# GDEnvSensorNode_1_4f.net
KiCad netlist of a schematic drawn in EAGLE
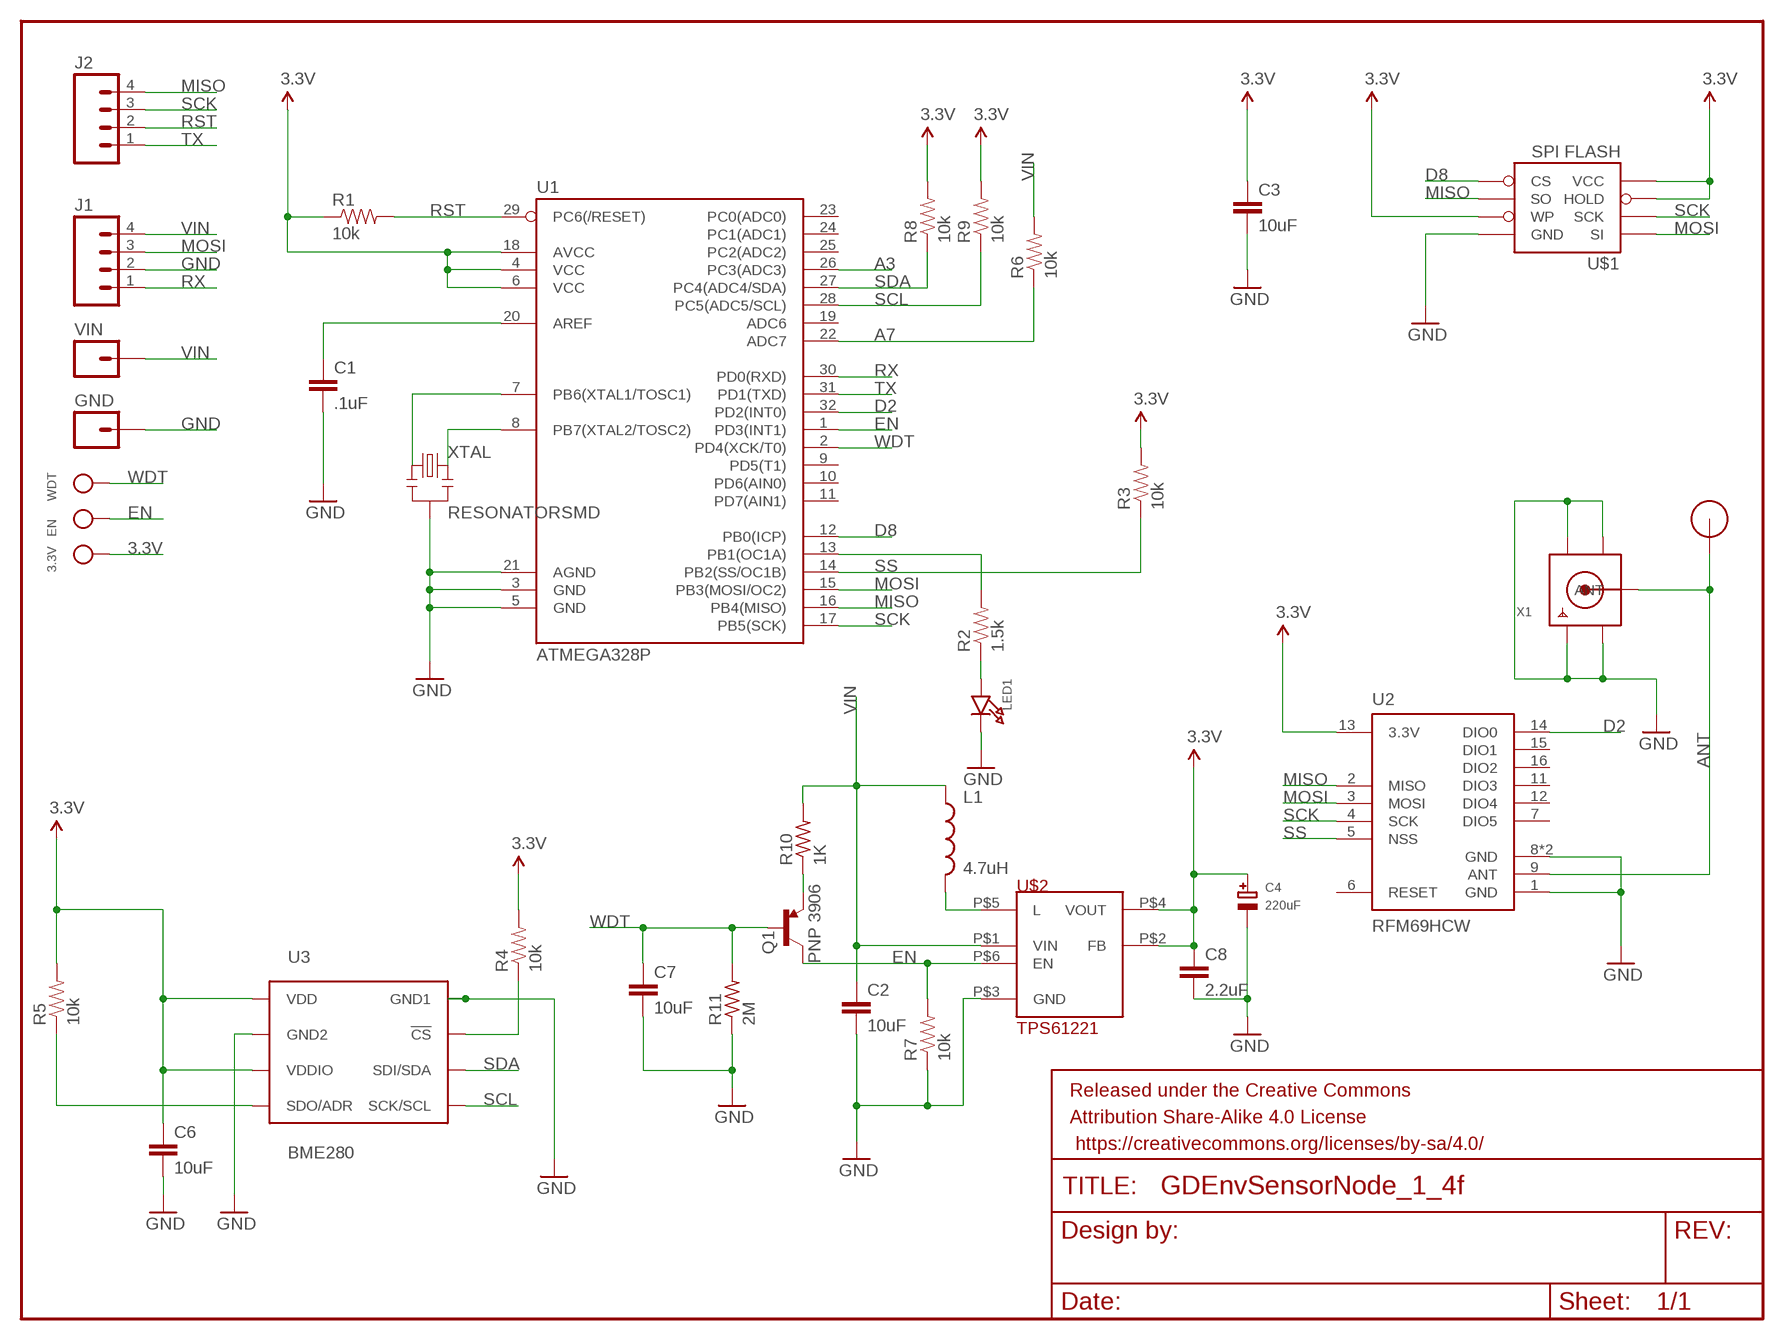
[diagram p0: schematic, sheet 1]

(export (version "E")
  (design (tool "Eeschema 10.0.6"))
  (components
    (comp (ref "3.3V")
      (value "TESTPOINTROUND1MM")
      (footprint "eagle-import:TESTPOINT_ROUND_1MM")
      (libsource (lib "eagle-import") (part "TESTPOINTROUND1MM"))
    )
    (comp (ref "C1")
      (value ".1uF")
      (footprint "eagle-import:0805")
      (libsource (lib "eagle-import") (part "CAP0805"))
    )
    (comp (ref "C2")
      (value "10uF")
      (footprint "eagle-import:0805")
      (libsource (lib "eagle-import") (part "CAP0805"))
    )
    (comp (ref "C3")
      (value "10uF")
      (footprint "eagle-import:0805")
      (libsource (lib "eagle-import") (part "CAP0805"))
    )
    (comp (ref "C4")
      (value "220uF")
      (footprint "eagle-import:EIA7343-31_D-R")
      (libsource (lib "eagle-import") (part "CAP_TANTALUMD/7343_REFLOW"))
    )
    (comp (ref "C6")
      (value "10uF")
      (footprint "eagle-import:0805")
      (libsource (lib "eagle-import") (part "CAP0805"))
    )
    (comp (ref "C7")
      (value "10uF")
      (footprint "eagle-import:0805")
      (libsource (lib "eagle-import") (part "CAP0805"))
    )
    (comp (ref "C8")
      (value "2.2uF")
      (footprint "eagle-import:0805")
      (libsource (lib "eagle-import") (part "CAP0805"))
    )
    (comp (ref "EN")
      (value "TESTPOINTROUND1MM")
      (footprint "eagle-import:TESTPOINT_ROUND_1MM")
      (libsource (lib "eagle-import") (part "TESTPOINTROUND1MM"))
    )
    (comp (ref "FRAME1")
      (value "FRAME-LETTER")
      (footprint "eagle-import:CREATIVE_COMMONS")
      (libsource (lib "eagle-import") (part "FRAME-LETTER"))
    )
    (comp (ref "GND")
      (value "M01PTH_2MM")
      (footprint "eagle-import:1X01_2MM")
      (libsource (lib "eagle-import") (part "M01PTH_2MM"))
    )
    (comp (ref "J1")
      (value "M04PTH")
      (footprint "eagle-import:1X04")
      (libsource (lib "eagle-import") (part "M04PTH"))
    )
    (comp (ref "J2")
      (value "M04PTH")
      (footprint "eagle-import:1X04")
      (libsource (lib "eagle-import") (part "M04PTH"))
    )
    (comp (ref "L1")
      (value "4.7uH")
      (footprint "eagle-import:1210")
      (libsource (lib "eagle-import") (part "INDUCTOR1210"))
    )
    (comp (ref "LED1")
      (value "LED0805")
      (footprint "eagle-import:CHIPLED_0805")
      (libsource (lib "eagle-import") (part "LED0805"))
    )
    (comp (ref "Q1")
      (value "PNP 3906")
      (footprint "eagle-import:SOT23-3")
      (libsource (lib "eagle-import") (part "TRANSISTOR_PNPPMBT3906"))
    )
    (comp (ref "R1")
      (value "10k")
      (footprint "eagle-import:0805")
      (libsource (lib "eagle-import") (part "RESISTOR0805-RES"))
    )
    (comp (ref "R2")
      (value "1.5k")
      (footprint "eagle-import:0805")
      (libsource (lib "eagle-import") (part "RESISTOR0805-RES"))
    )
    (comp (ref "R3")
      (value "10k")
      (footprint "eagle-import:0805")
      (libsource (lib "eagle-import") (part "RESISTOR0805-RES"))
    )
    (comp (ref "R4")
      (value "10k")
      (footprint "eagle-import:0805")
      (libsource (lib "eagle-import") (part "RESISTOR0805-RES"))
    )
    (comp (ref "R5")
      (value "10k")
      (footprint "eagle-import:0805")
      (libsource (lib "eagle-import") (part "RESISTOR0805-RES"))
    )
    (comp (ref "R6")
      (value "10k")
      (footprint "eagle-import:0805")
      (libsource (lib "eagle-import") (part "RESISTOR0805-RES"))
    )
    (comp (ref "R7")
      (value "10k")
      (footprint "eagle-import:0805")
      (libsource (lib "eagle-import") (part "RESISTOR0805-RES"))
    )
    (comp (ref "R8")
      (value "10k")
      (footprint "eagle-import:0805")
      (libsource (lib "eagle-import") (part "RESISTOR0805-RES"))
    )
    (comp (ref "R9")
      (value "10k")
      (footprint "eagle-import:0805")
      (libsource (lib "eagle-import") (part "RESISTOR0805-RES"))
    )
    (comp (ref "R10")
      (value "1K")
      (footprint "eagle-import:R0805")
      (libsource (lib "eagle-import") (part "R-US_R0805"))
    )
    (comp (ref "R11")
      (value "2M")
      (footprint "eagle-import:R0805")
      (libsource (lib "eagle-import") (part "R-US_R0805"))
    )
    (comp (ref "U$1")
      (value "SPI FLASH")
      (footprint "eagle-import:SO08")
      (libsource (lib "eagle-import") (part "AT25F512BJEDEC_3.9MM"))
    )
    (comp (ref "U$2")
      (value "TPS61221")
      (footprint "eagle-import:TPS61221")
      (fields (field (name "MF") "Texas Instruments"))
      (libsource (lib "eagle-import") (part "TPS61221"))
    )
    (comp (ref "U$4")
      (value "RFM12B_ANTENNA")
      (footprint "eagle-import:RFM12B-ANTENNA")
      (libsource (lib "eagle-import") (part "RFM12B_ANTENNA"))
    )
    (comp (ref "U1")
      (value "ATMEGA328P")
      (footprint "eagle-import:TQFP32-08")
      (libsource (lib "eagle-import") (part "ATMEGA328P_TQFP"))
    )
    (comp (ref "U2")
      (value "RFM69HCW")
      (footprint "eagle-import:RFM69HCW-XXXS2")
      (libsource (lib "eagle-import") (part "RFM69HCW"))
    )
    (comp (ref "U3")
      (value "BME280")
      (footprint "eagle-import:BME280_LGA")
      (libsource (lib "eagle-import") (part "BME280"))
    )
    (comp (ref "VIN")
      (value "M01PTH_2MM")
      (footprint "eagle-import:1X01_2MM")
      (libsource (lib "eagle-import") (part "M01PTH_2MM"))
    )
    (comp (ref "WDT")
      (value "TESTPOINTROUND1MM")
      (footprint "eagle-import:TESTPOINT_ROUND_1MM")
      (libsource (lib "eagle-import") (part "TESTPOINTROUND1MM"))
    )
    (comp (ref "X1")
      (value "SMACONNECTOR_EDGE_UFL")
      (footprint "eagle-import:SMA_EDGELAUNCH_UFL")
      (libsource (lib "eagle-import") (part "SMACONNECTOR_EDGE_UFL"))
    )
    (comp (ref "XTAL")
      (value "RESONATORSMD")
      (footprint "eagle-import:RESONATOR-SMD")
      (libsource (lib "eagle-import") (part "RESONATORSMD"))
    )
  )
  (nets
    (net (code "1") (name "/A3") (class "Default")
      (node (ref "U1") (pin "26") (pinfunction "PC3(ADC3)_26") (pintype "bidirectional"))
    )
    (net (code "2") (name "/A7") (class "Default")
      (node (ref "R6") (pin "1") (pinfunction "1_1") (pintype "passive"))
      (node (ref "U1") (pin "22") (pinfunction "ADC7_22") (pintype "bidirectional"))
    )
    (net (code "3") (name "/ANT") (class "Default")
      (node (ref "U$4") (pin "P$1") (pinfunction "1_P$1") (pintype "bidirectional"))
      (node (ref "U2") (pin "9") (pinfunction "ANT_9") (pintype "passive"))
      (node (ref "X1") (pin "P") (pinfunction "ANT_P") (pintype "bidirectional"))
    )
    (net (code "4") (name "/D2") (class "Default")
      (node (ref "U1") (pin "32") (pinfunction "PD2(INT0)_32") (pintype "bidirectional"))
      (node (ref "U2") (pin "14") (pinfunction "DIO0_14") (pintype "bidirectional"))
    )
    (net (code "5") (name "/D8") (class "Default")
      (node (ref "U$1") (pin "1_CS") (pinfunction "CS_1_CS") (pintype "bidirectional"))
      (node (ref "U1") (pin "12") (pinfunction "PB0(ICP)_12") (pintype "bidirectional"))
    )
    (net (code "6") (name "/EN") (class "Default")
      (node (ref "EN") (pin "P$1") (pinfunction "P$1_P$1") (pintype "bidirectional"))
      (node (ref "Q1") (pin "3") (pinfunction "C_3") (pintype "passive"))
      (node (ref "R7") (pin "2") (pinfunction "2_2") (pintype "passive"))
      (node (ref "U$2") (pin "P$6") (pinfunction "EN_P$6") (pintype "bidirectional"))
      (node (ref "U1") (pin "1") (pinfunction "PD3(INT1)_1") (pintype "bidirectional"))
    )
    (net (code "7") (name "/MISO") (class "Default")
      (node (ref "J2") (pin "4") (pinfunction "4_4") (pintype "passive"))
      (node (ref "U$1") (pin "2_SO") (pinfunction "SO_2_SO") (pintype "bidirectional"))
      (node (ref "U1") (pin "16") (pinfunction "PB4(MISO)_16") (pintype "bidirectional"))
      (node (ref "U2") (pin "2") (pinfunction "MISO_2") (pintype "bidirectional"))
    )
    (net (code "8") (name "/MOSI") (class "Default")
      (node (ref "J1") (pin "3") (pinfunction "3_3") (pintype "passive"))
      (node (ref "U$1") (pin "5_SI") (pinfunction "SI_5_SI") (pintype "bidirectional"))
      (node (ref "U1") (pin "15") (pinfunction "PB3(MOSI/OC2)_15") (pintype "bidirectional"))
      (node (ref "U2") (pin "3") (pinfunction "MOSI_3") (pintype "input"))
    )
    (net (code "9") (name "/RST") (class "Default")
      (node (ref "J2") (pin "2") (pinfunction "2_2") (pintype "passive"))
      (node (ref "R1") (pin "2") (pinfunction "2_2") (pintype "passive"))
      (node (ref "U1") (pin "29") (pinfunction "PC6(/RESET)_29") (pintype "bidirectional"))
    )
    (net (code "10") (name "/RX") (class "Default")
      (node (ref "J1") (pin "1") (pinfunction "1_1") (pintype "passive"))
      (node (ref "U1") (pin "30") (pinfunction "PD0(RXD)_30") (pintype "bidirectional"))
    )
    (net (code "11") (name "/SCK") (class "Default")
      (node (ref "J2") (pin "3") (pinfunction "3_3") (pintype "passive"))
      (node (ref "U$1") (pin "6_SCK") (pinfunction "SCK_6_SCK") (pintype "bidirectional"))
      (node (ref "U1") (pin "17") (pinfunction "PB5(SCK)_17") (pintype "bidirectional"))
      (node (ref "U2") (pin "4") (pinfunction "SCK_4") (pintype "input"))
    )
    (net (code "12") (name "/SCL") (class "Default")
      (node (ref "R9") (pin "1") (pinfunction "1_1") (pintype "passive"))
      (node (ref "U1") (pin "28") (pinfunction "PC5(ADC5/SCL)_28") (pintype "bidirectional"))
      (node (ref "U3") (pin "P$4") (pinfunction "SCK/SCL_P$4") (pintype "bidirectional"))
    )
    (net (code "13") (name "/SDA") (class "Default")
      (node (ref "R8") (pin "1") (pinfunction "1_1") (pintype "passive"))
      (node (ref "U1") (pin "27") (pinfunction "PC4(ADC4/SDA)_27") (pintype "bidirectional"))
      (node (ref "U3") (pin "P$3") (pinfunction "SDI/SDA_P$3") (pintype "bidirectional"))
    )
    (net (code "14") (name "/SS") (class "Default")
      (node (ref "R3") (pin "1") (pinfunction "1_1") (pintype "passive"))
      (node (ref "U1") (pin "14") (pinfunction "PB2(SS/OC1B)_14") (pintype "bidirectional"))
      (node (ref "U2") (pin "5") (pinfunction "NSS_5") (pintype "input"))
    )
    (net (code "15") (name "/TX") (class "Default")
      (node (ref "J2") (pin "1") (pinfunction "1_1") (pintype "passive"))
      (node (ref "U1") (pin "31") (pinfunction "PD1(TXD)_31") (pintype "bidirectional"))
    )
    (net (code "16") (name "/VIN") (class "Default")
      (node (ref "C2") (pin "1") (pinfunction "1_1") (pintype "passive"))
      (node (ref "J1") (pin "4") (pinfunction "4_4") (pintype "passive"))
      (node (ref "L1") (pin "1") (pinfunction "1_1") (pintype "passive"))
      (node (ref "R10") (pin "2") (pinfunction "2_2") (pintype "passive"))
      (node (ref "R6") (pin "2") (pinfunction "2_2") (pintype "passive"))
      (node (ref "U$2") (pin "P$1") (pinfunction "VIN_P$1") (pintype "bidirectional"))
      (node (ref "VIN") (pin "1") (pinfunction "1_1") (pintype "passive"))
    )
    (net (code "17") (name "/WDT") (class "Default")
      (node (ref "C7") (pin "1") (pinfunction "1_1") (pintype "passive"))
      (node (ref "Q1") (pin "1") (pinfunction "B_1") (pintype "passive"))
      (node (ref "R11") (pin "2") (pinfunction "2_2") (pintype "passive"))
      (node (ref "U1") (pin "2") (pinfunction "PD4(XCK/T0)_2") (pintype "bidirectional"))
      (node (ref "WDT") (pin "P$1") (pinfunction "P$1_P$1") (pintype "bidirectional"))
    )
    (net (code "18") (name "3.3V") (class "Default")
      (node (ref "3.3V") (pin "P$1") (pinfunction "P$1_P$1") (pintype "bidirectional"))
      (node (ref "C3") (pin "1") (pinfunction "1_1") (pintype "passive"))
      (node (ref "C4") (pin "+") (pinfunction "+_+") (pintype "passive"))
      (node (ref "C6") (pin "1") (pinfunction "1_1") (pintype "passive"))
      (node (ref "C8") (pin "1") (pinfunction "1_1") (pintype "passive"))
      (node (ref "R1") (pin "1") (pinfunction "1_1") (pintype "passive"))
      (node (ref "R3") (pin "2") (pinfunction "2_2") (pintype "passive"))
      (node (ref "R4") (pin "2") (pinfunction "2_2") (pintype "passive"))
      (node (ref "R5") (pin "2") (pinfunction "2_2") (pintype "passive"))
      (node (ref "R8") (pin "2") (pinfunction "2_2") (pintype "passive"))
      (node (ref "R9") (pin "2") (pinfunction "2_2") (pintype "passive"))
      (node (ref "U$1") (pin "3_WP") (pinfunction "WP_3_WP") (pintype "bidirectional"))
      (node (ref "U$1") (pin "7_HOLD") (pinfunction "HOLD_7_HOLD") (pintype "bidirectional"))
      (node (ref "U$1") (pin "8_VCC") (pinfunction "VCC_8_VCC") (pintype "bidirectional"))
      (node (ref "U$2") (pin "P$2") (pinfunction "FB_P$2") (pintype "bidirectional"))
      (node (ref "U$2") (pin "P$4") (pinfunction "VOUT_P$4") (pintype "bidirectional"))
      (node (ref "U1") (pin "18") (pinfunction "AVCC_18") (pintype "bidirectional"))
      (node (ref "U1") (pin "4") (pinfunction "VCC_4") (pintype "bidirectional"))
      (node (ref "U1") (pin "6") (pinfunction "VCC_6") (pintype "bidirectional"))
      (node (ref "U2") (pin "13") (pinfunction "3.3V_13") (pintype "power_in"))
      (node (ref "U3") (pin "P$6") (pinfunction "VDDIO_P$6") (pintype "bidirectional"))
      (node (ref "U3") (pin "P$8") (pinfunction "VDD_P$8") (pintype "bidirectional"))
    )
    (net (code "19") (name "GND") (class "Default")
      (node (ref "C1") (pin "2") (pinfunction "2_2") (pintype "passive"))
      (node (ref "C2") (pin "2") (pinfunction "2_2") (pintype "passive"))
      (node (ref "C3") (pin "2") (pinfunction "2_2") (pintype "passive"))
      (node (ref "C4") (pin "-") (pinfunction "-_-") (pintype "passive"))
      (node (ref "C6") (pin "2") (pinfunction "2_2") (pintype "passive"))
      (node (ref "C7") (pin "2") (pinfunction "2_2") (pintype "passive"))
      (node (ref "C8") (pin "2") (pinfunction "2_2") (pintype "passive"))
      (node (ref "GND") (pin "1") (pinfunction "1_1") (pintype "passive"))
      (node (ref "J1") (pin "2") (pinfunction "2_2") (pintype "passive"))
      (node (ref "LED1") (pin "C") (pinfunction "C_C") (pintype "passive"))
      (node (ref "R11") (pin "1") (pinfunction "1_1") (pintype "passive"))
      (node (ref "R7") (pin "1") (pinfunction "1_1") (pintype "passive"))
      (node (ref "U$1") (pin "4_GND") (pinfunction "GND_4_GND") (pintype "bidirectional"))
      (node (ref "U$2") (pin "P$3") (pinfunction "GND_P$3") (pintype "bidirectional"))
      (node (ref "U1") (pin "21") (pinfunction "AGND_21") (pintype "bidirectional"))
      (node (ref "U1") (pin "3") (pinfunction "GND_3") (pintype "bidirectional"))
      (node (ref "U1") (pin "5") (pinfunction "GND_5") (pintype "bidirectional"))
      (node (ref "U2") (pin "1") (pinfunction "GND_1") (pintype "power_in"))
      (node (ref "U2") (pin "10") (pinfunction "GND_10") (pintype "power_in"))
      (node (ref "U2") (pin "8") (pinfunction "GND_8") (pintype "power_in"))
      (node (ref "U3") (pin "P$1") (pinfunction "GND1_P$1") (pintype "bidirectional"))
      (node (ref "U3") (pin "P$7") (pinfunction "GND2_P$7") (pintype "bidirectional"))
      (node (ref "X1") (pin "GND@1") (pinfunction "GND1_GND@1") (pintype "power_in"))
      (node (ref "X1") (pin "GND@2") (pinfunction "GND2_GND@2") (pintype "power_in"))
      (node (ref "X1") (pin "GND@3") (pinfunction "GND3_GND@3") (pintype "power_in"))
      (node (ref "X1") (pin "GND@4") (pinfunction "GND4_GND@4") (pintype "power_in"))
      (node (ref "XTAL") (pin "2") (pinfunction "2_2") (pintype "passive"))
    )
    (net (code "20") (name "Net-(LED1-PadA)") (class "Default")
      (node (ref "LED1") (pin "A") (pinfunction "A_A") (pintype "passive"))
      (node (ref "R2") (pin "1") (pinfunction "1_1") (pintype "passive"))
    )
    (net (code "21") (name "Net-(Q1-E)") (class "Default")
      (node (ref "Q1") (pin "2") (pinfunction "E_2") (pintype "passive"))
      (node (ref "R10") (pin "1") (pinfunction "1_1") (pintype "passive"))
    )
    (net (code "22") (name "Net-(U$2-L)") (class "Default")
      (node (ref "L1") (pin "2") (pinfunction "2_2") (pintype "passive"))
      (node (ref "U$2") (pin "P$5") (pinfunction "L_P$5") (pintype "bidirectional"))
    )
    (net (code "23") (name "Net-(U1-AREF)") (class "Default")
      (node (ref "C1") (pin "1") (pinfunction "1_1") (pintype "passive"))
      (node (ref "U1") (pin "20") (pinfunction "AREF_20") (pintype "bidirectional"))
    )
    (net (code "24") (name "Net-(U1-PB1(OC1A))") (class "Default")
      (node (ref "R2") (pin "2") (pinfunction "2_2") (pintype "passive"))
      (node (ref "U1") (pin "13") (pinfunction "PB1(OC1A)_13") (pintype "bidirectional"))
    )
    (net (code "25") (name "Net-(U1-PB6(XTAL1{slash}TOSC1))") (class "Default")
      (node (ref "U1") (pin "7") (pinfunction "PB6(XTAL1/TOSC1)_7") (pintype "bidirectional"))
      (node (ref "XTAL") (pin "1") (pinfunction "1_1") (pintype "passive"))
    )
    (net (code "26") (name "Net-(U1-PB7(XTAL2{slash}TOSC2))") (class "Default")
      (node (ref "U1") (pin "8") (pinfunction "PB7(XTAL2/TOSC2)_8") (pintype "bidirectional"))
      (node (ref "XTAL") (pin "3") (pinfunction "3_3") (pintype "passive"))
    )
    (net (code "27") (name "Net-(U3-SDO{slash}ADR)") (class "Default")
      (node (ref "R5") (pin "1") (pinfunction "1_1") (pintype "passive"))
      (node (ref "U3") (pin "P$5") (pinfunction "SDO/ADR_P$5") (pintype "bidirectional"))
    )
    (net (code "28") (name "Net-(U3-~{CS})") (class "Default")
      (node (ref "R4") (pin "1") (pinfunction "1_1") (pintype "passive"))
      (node (ref "U3") (pin "P$2") (pinfunction "~{CS}_P$2") (pintype "bidirectional"))
    )
    (net (code "29") (name "unconnected-(U1-ADC6-Pad19)") (class "Default")
      (node (ref "U1") (pin "19") (pinfunction "ADC6_19") (pintype "bidirectional"))
    )
    (net (code "30") (name "unconnected-(U1-PC0(ADC0)-Pad23)") (class "Default")
      (node (ref "U1") (pin "23") (pinfunction "PC0(ADC0)_23") (pintype "bidirectional"))
    )
    (net (code "31") (name "unconnected-(U1-PC1(ADC1)-Pad24)") (class "Default")
      (node (ref "U1") (pin "24") (pinfunction "PC1(ADC1)_24") (pintype "bidirectional"))
    )
    (net (code "32") (name "unconnected-(U1-PC2(ADC2)-Pad25)") (class "Default")
      (node (ref "U1") (pin "25") (pinfunction "PC2(ADC2)_25") (pintype "bidirectional"))
    )
    (net (code "33") (name "unconnected-(U1-PD5(T1)-Pad9)") (class "Default")
      (node (ref "U1") (pin "9") (pinfunction "PD5(T1)_9") (pintype "bidirectional"))
    )
    (net (code "34") (name "unconnected-(U1-PD6(AIN0)-Pad10)") (class "Default")
      (node (ref "U1") (pin "10") (pinfunction "PD6(AIN0)_10") (pintype "bidirectional"))
    )
    (net (code "35") (name "unconnected-(U1-PD7(AIN1)-Pad11)") (class "Default")
      (node (ref "U1") (pin "11") (pinfunction "PD7(AIN1)_11") (pintype "bidirectional"))
    )
    (net (code "36") (name "unconnected-(U2-DIO1-Pad15)") (class "Default")
      (node (ref "U2") (pin "15") (pinfunction "DIO1_15") (pintype "bidirectional"))
    )
    (net (code "37") (name "unconnected-(U2-DIO2-Pad16)") (class "Default")
      (node (ref "U2") (pin "16") (pinfunction "DIO2_16") (pintype "bidirectional"))
    )
    (net (code "38") (name "unconnected-(U2-DIO3-Pad11)") (class "Default")
      (node (ref "U2") (pin "11") (pinfunction "DIO3_11") (pintype "bidirectional"))
    )
    (net (code "39") (name "unconnected-(U2-DIO4-Pad12)") (class "Default")
      (node (ref "U2") (pin "12") (pinfunction "DIO4_12") (pintype "bidirectional"))
    )
    (net (code "40") (name "unconnected-(U2-DIO5-Pad7)") (class "Default")
      (node (ref "U2") (pin "7") (pinfunction "DIO5_7") (pintype "bidirectional"))
    )
    (net (code "41") (name "unconnected-(U2-RESET-Pad6)") (class "Default")
      (node (ref "U2") (pin "6") (pinfunction "RESET_6") (pintype "input"))
    )
  )
)
